# micro.net
KiCad netlist of a schematic drawn in Altium Designer
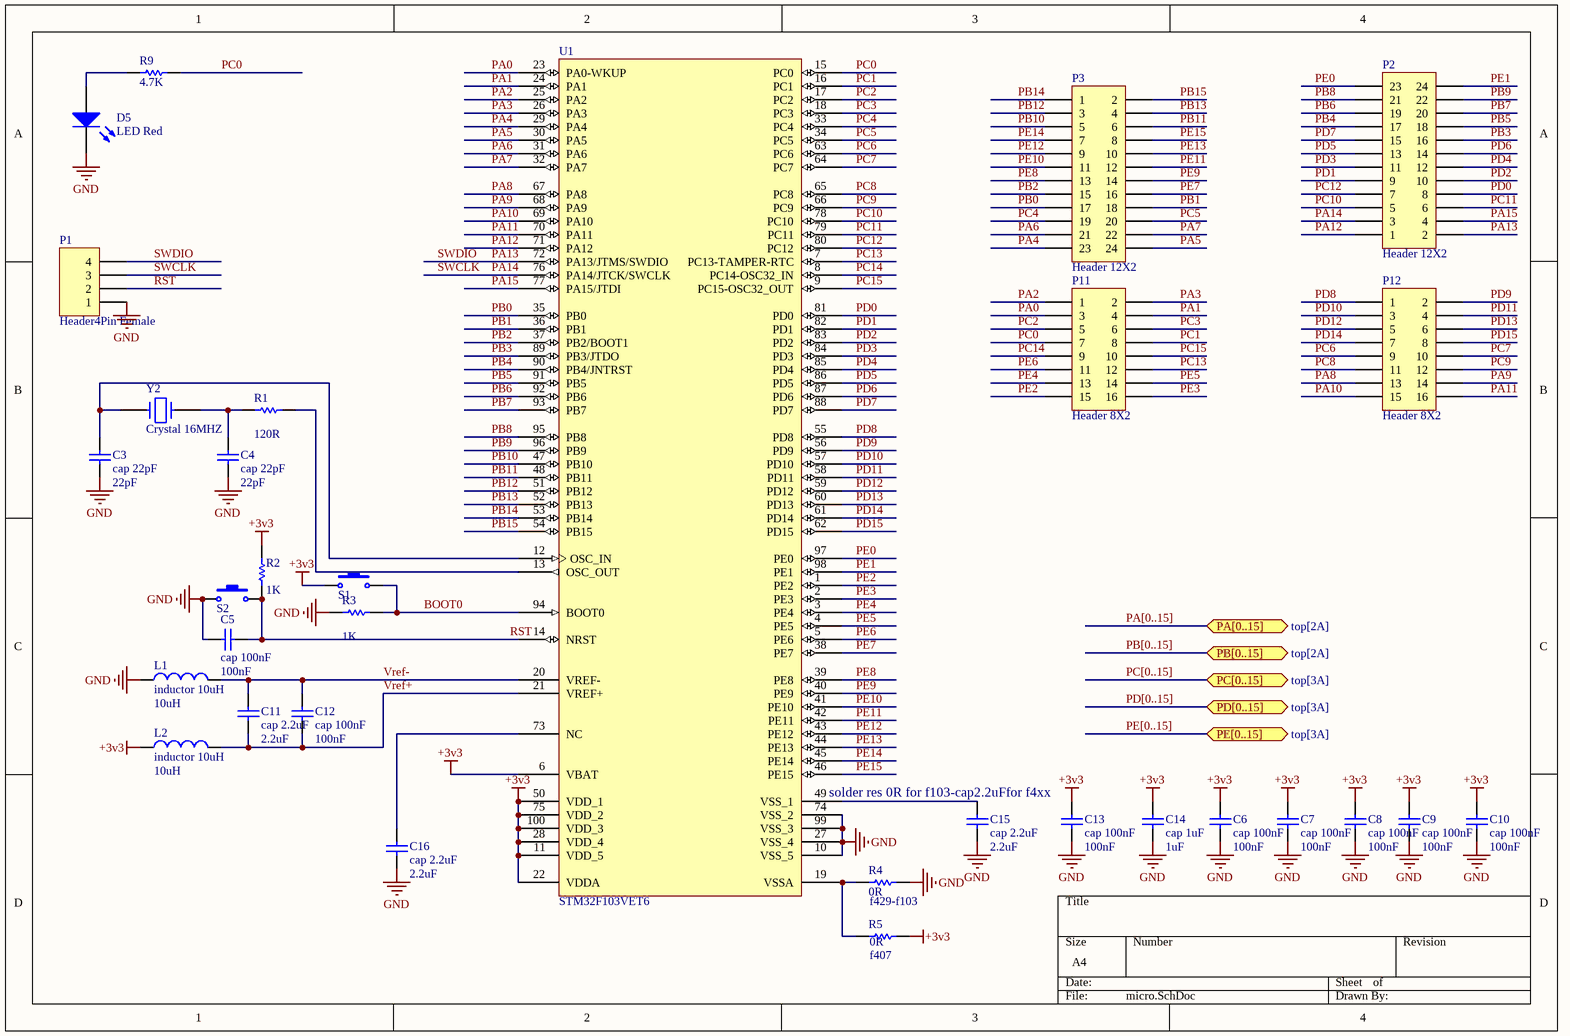
[diagram p0: micro.SchDoc]

(export (version "E")
  (design (tool "Eeschema 10.0.6"))
  (components
    (comp (ref "C3")
      (value "cap 22pF")
      (footprint "Cap 805")
      (description "Capacitor")
      (fields (field (name "ALTIUM_VALUE") "22pF") (field (name "PUBLISHER") "Altium Limited"))
      (libsource (lib "Miscellaneous Devices") (part "Cap"))
    )
    (comp (ref "C4")
      (value "cap 22pF")
      (footprint "Cap 805")
      (description "Capacitor")
      (fields (field (name "ALTIUM_VALUE") "22pF") (field (name "PUBLISHER") "Altium Limited"))
      (libsource (lib "Miscellaneous Devices") (part "Cap"))
    )
    (comp (ref "C5")
      (value "cap 100nF")
      (footprint "Cap 805")
      (description "Capacitor")
      (fields (field (name "ALTIUM_VALUE") "100nF") (field (name "PUBLISHER") "Altium Limited"))
      (libsource (lib "Miscellaneous Devices") (part "Cap"))
    )
    (comp (ref "C6")
      (value "cap 100nF")
      (footprint "Cap 805")
      (description "Capacitor")
      (fields (field (name "ALTIUM_VALUE") "100nF") (field (name "PUBLISHER") "Altium Limited"))
      (libsource (lib "Miscellaneous Devices") (part "Cap"))
    )
    (comp (ref "C7")
      (value "cap 100nF")
      (footprint "Cap 805")
      (description "Capacitor")
      (fields (field (name "ALTIUM_VALUE") "100nF") (field (name "PUBLISHER") "Altium Limited"))
      (libsource (lib "Miscellaneous Devices") (part "Cap"))
    )
    (comp (ref "C8")
      (value "cap 100nF")
      (footprint "Cap 805")
      (description "Capacitor")
      (fields (field (name "ALTIUM_VALUE") "100nF") (field (name "PUBLISHER") "Altium Limited"))
      (libsource (lib "Miscellaneous Devices") (part "Cap"))
    )
    (comp (ref "C9")
      (value "cap 100nF")
      (footprint "Cap 805")
      (description "Capacitor")
      (fields (field (name "ALTIUM_VALUE") "100nF") (field (name "PUBLISHER") "Altium Limited"))
      (libsource (lib "Miscellaneous Devices") (part "Cap"))
    )
    (comp (ref "C10")
      (value "cap 100nF")
      (footprint "Cap 805")
      (description "Capacitor")
      (fields (field (name "ALTIUM_VALUE") "100nF") (field (name "PUBLISHER") "Altium Limited"))
      (libsource (lib "Miscellaneous Devices") (part "Cap"))
    )
    (comp (ref "C11")
      (value "cap 2.2uF")
      (footprint "Cap 805")
      (description "Capacitor")
      (fields (field (name "ALTIUM_VALUE") "2.2uF") (field (name "PUBLISHER") "Altium Limited"))
      (libsource (lib "Miscellaneous Devices") (part "Cap"))
    )
    (comp (ref "C12")
      (value "cap 100nF")
      (footprint "Cap 805")
      (description "Capacitor")
      (fields (field (name "ALTIUM_VALUE") "100nF") (field (name "PUBLISHER") "Altium Limited"))
      (libsource (lib "Miscellaneous Devices") (part "Cap"))
    )
    (comp (ref "C13")
      (value "cap 100nF")
      (footprint "Cap 805")
      (description "Capacitor")
      (fields (field (name "ALTIUM_VALUE") "100nF") (field (name "PUBLISHER") "Altium Limited"))
      (libsource (lib "Miscellaneous Devices") (part "Cap"))
    )
    (comp (ref "C14")
      (value "cap 1uF")
      (footprint "Cap 805")
      (description "Capacitor")
      (fields (field (name "ALTIUM_VALUE") "1uF") (field (name "PUBLISHER") "Altium Limited"))
      (libsource (lib "Miscellaneous Devices") (part "Cap"))
    )
    (comp (ref "C15")
      (value "cap 2.2uF")
      (footprint "Cap 805")
      (description "Capacitor")
      (fields (field (name "ALTIUM_VALUE") "2.2uF") (field (name "PUBLISHER") "Altium Limited"))
      (libsource (lib "Miscellaneous Devices") (part "Cap"))
    )
    (comp (ref "C16")
      (value "cap 2.2uF")
      (footprint "Cap 805")
      (description "Capacitor")
      (fields (field (name "ALTIUM_VALUE") "2.2uF") (field (name "PUBLISHER") "Altium Limited"))
      (libsource (lib "Miscellaneous Devices") (part "Cap"))
    )
    (comp (ref "D5")
      (value "LED Red")
      (footprint "0805-LED")
      (description "LED SMD")
      (fields (field (name "PUBLISHER") "Altium Limited"))
      (libsource (lib "Miscellaneous Devices") (part "LED0"))
    )
    (comp (ref "L1")
      (value "inductor 10uH")
      (footprint "IND1206")
      (description "Inductor")
      (fields (field (name "ALTIUM_VALUE") "10uH") (field (name "PUBLISHER") "Altium Limited"))
      (libsource (lib "Miscellaneous Devices") (part "Inductor"))
    )
    (comp (ref "L2")
      (value "inductor 10uH")
      (footprint "IND1206")
      (description "Inductor")
      (fields (field (name "ALTIUM_VALUE") "10uH") (field (name "PUBLISHER") "Altium Limited"))
      (libsource (lib "Miscellaneous Devices") (part "Inductor"))
    )
    (comp (ref "P1")
      (value "Header4Pin Female")
      (footprint "HDR1X4")
      (description "Header, 4-Pin")
      (fields (field (name "PUBLISHER") "Altium Limited"))
      (libsource (lib "Miscellaneous Connectors") (part "Header 4"))
    )
    (comp (ref "P2")
      (value "Header 12X2")
      (footprint "HDR2X12")
      (description "Header, 12-Pin, Dual row")
      (fields (field (name "PUBLISHER") "Altium Limited"))
      (libsource (lib "") (part "Header 12X2_1"))
    )
    (comp (ref "P3")
      (value "Header 12X2")
      (footprint "HDR2X12")
      (description "Header, 12-Pin, Dual row")
      (fields (field (name "PUBLISHER") "Altium Limited"))
      (libsource (lib "Miscellaneous Connectors") (part "Header 12X2"))
    )
    (comp (ref "P11")
      (value "Header 8X2")
      (footprint "HDR2X8")
      (description "Header, 8-Pin, Dual row")
      (fields (field (name "PUBLISHER") "Altium Limited"))
      (libsource (lib "Miscellaneous Connectors") (part "Header 8X2"))
    )
    (comp (ref "P12")
      (value "Header 8X2")
      (footprint "HDR2X8")
      (description "Header, 8-Pin, Dual row")
      (fields (field (name "PUBLISHER") "Altium Limited"))
      (libsource (lib "Miscellaneous Connectors") (part "Header 8X2"))
    )
    (comp (ref "R1")
      (value "120R")
      (footprint "RES 0805 (2012X06L)")
      (description "Resistor")
      (fields (field (name "Comment") "Res 120R") (field (name "PUBLISHER") "Altium Limited"))
      (libsource (lib "Miscellaneous Devices") (part "Res1"))
    )
    (comp (ref "R2")
      (value "1K")
      (footprint "RES 0805 (2012X06L)")
      (description "Resistor")
      (fields (field (name "Comment") "Res 1K") (field (name "PUBLISHER") "Altium Limited"))
      (libsource (lib "Miscellaneous Devices") (part "Res1"))
    )
    (comp (ref "R3")
      (value "1K")
      (footprint "RES 0805 (2012X06L)")
      (description "Resistor")
      (fields (field (name "Comment") "Res 1K") (field (name "PUBLISHER") "Altium Limited"))
      (libsource (lib "Miscellaneous Devices") (part "Res1"))
    )
    (comp (ref "R4")
      (value "f429-f103")
      (footprint "RES 0805 (2012X06L)")
      (description "Resistor")
      (fields (field (name "ALTIUM_VALUE") "0R") (field (name "PUBLISHER") "Altium Limited"))
      (libsource (lib "Miscellaneous Devices") (part "Res1"))
    )
    (comp (ref "R5")
      (value "f407")
      (footprint "RES 0805 (2012X06L)")
      (description "Resistor")
      (fields (field (name "ALTIUM_VALUE") "0R") (field (name "PUBLISHER") "Altium Limited"))
      (libsource (lib "Miscellaneous Devices") (part "Res1"))
    )
    (comp (ref "R9")
      (value "4.7K")
      (footprint "RES 0805 (2012X06L)")
      (description "Resistor")
      (fields (field (name "Comment") "Res 4.7K") (field (name "PUBLISHER") "Altium Limited"))
      (libsource (lib "Miscellaneous Devices") (part "Res1"))
    )
    (comp (ref "S1")
      (value "Switch PB")
      (footprint "Switch - Push to On")
      (description "Push Button Switch")
      (libsource (lib "Altium (2)") (part "Switch PB"))
    )
    (comp (ref "S2")
      (value "Switch PB")
      (footprint "Switch - Push to On")
      (description "Push Button Switch")
      (libsource (lib "Altium (2)") (part "Switch PB"))
    )
    (comp (ref "U1")
      (value "STM32F103VET6")
      (footprint "LQFP100_N")
      (description "STM32 ARM-based 32-bit MCU with 64 Kbytes Flash, 100-pin LQFP, Industrial Temperature")
      (fields (field (name "PUBLISHER") "Altium Limited"))
      (libsource (lib "ST Microcontroller 32-Bit STM32") (part "STM32F103V8T6"))
    )
    (comp (ref "Y2")
      (value "Crystal 16MHZ")
      (footprint "CRYSTAL Small")
      (description "Crystal")
      (libsource (lib "Altium library (www.AVRelec.com)") (part "CRYSTAL"))
    )
  )
  (nets
    (net (code "1") (name "+3v3") (class "Default")
      (node (ref "C10") (pin "2") (pinfunction "2_2") (pintype "passive"))
      (node (ref "C13") (pin "2") (pinfunction "2_2") (pintype "passive"))
      (node (ref "C14") (pin "2") (pinfunction "2_2") (pintype "passive"))
      (node (ref "C6") (pin "2") (pinfunction "2_2") (pintype "passive"))
      (node (ref "C7") (pin "2") (pinfunction "2_2") (pintype "passive"))
      (node (ref "C8") (pin "2") (pinfunction "2_2") (pintype "passive"))
      (node (ref "C9") (pin "2") (pinfunction "2_2") (pintype "passive"))
      (node (ref "L2") (pin "1") (pinfunction "1_1") (pintype "passive"))
      (node (ref "R2") (pin "1") (pinfunction "1_1") (pintype "passive"))
      (node (ref "R5") (pin "2") (pinfunction "2_2") (pintype "passive"))
      (node (ref "S1") (pin "1") (pinfunction "1_1") (pintype "passive"))
      (node (ref "U1") (pin "100") (pinfunction "VDD_3_100") (pintype "power_in"))
      (node (ref "U1") (pin "11") (pinfunction "VDD_5_11") (pintype "power_in"))
      (node (ref "U1") (pin "22") (pinfunction "VDDA_22") (pintype "power_in"))
      (node (ref "U1") (pin "28") (pinfunction "VDD_4_28") (pintype "power_in"))
      (node (ref "U1") (pin "50") (pinfunction "VDD_1_50") (pintype "power_in"))
      (node (ref "U1") (pin "6") (pinfunction "VBAT_6") (pintype "power_in"))
      (node (ref "U1") (pin "75") (pinfunction "VDD_2_75") (pintype "power_in"))
    )
    (net (code "2") (name "/BOOT0") (class "Default")
      (node (ref "R3") (pin "2") (pinfunction "2_2") (pintype "passive"))
      (node (ref "S1") (pin "2") (pinfunction "2_2") (pintype "passive"))
      (node (ref "U1") (pin "94") (pinfunction "BOOT0_94") (pintype "input"))
    )
    (net (code "3") (name "/PA0") (class "Default")
      (node (ref "P11") (pin "3") (pinfunction "3_3") (pintype "passive"))
      (node (ref "U1") (pin "23") (pinfunction "PA0-WKUP_23") (pintype "bidirectional"))
    )
    (net (code "4") (name "/PA1") (class "Default")
      (node (ref "P11") (pin "4") (pinfunction "4_4") (pintype "passive"))
      (node (ref "U1") (pin "24") (pinfunction "PA1_24") (pintype "bidirectional"))
    )
    (net (code "5") (name "/PA2") (class "Default")
      (node (ref "P11") (pin "1") (pinfunction "1_1") (pintype "passive"))
      (node (ref "U1") (pin "25") (pinfunction "PA2_25") (pintype "bidirectional"))
    )
    (net (code "6") (name "/PA3") (class "Default")
      (node (ref "P11") (pin "2") (pinfunction "2_2") (pintype "passive"))
      (node (ref "U1") (pin "26") (pinfunction "PA3_26") (pintype "bidirectional"))
    )
    (net (code "7") (name "/PA4") (class "Default")
      (node (ref "P3") (pin "23") (pinfunction "23_23") (pintype "passive"))
      (node (ref "U1") (pin "29") (pinfunction "PA4_29") (pintype "bidirectional"))
    )
    (net (code "8") (name "/PA5") (class "Default")
      (node (ref "P3") (pin "24") (pinfunction "24_24") (pintype "passive"))
      (node (ref "U1") (pin "30") (pinfunction "PA5_30") (pintype "bidirectional"))
    )
    (net (code "9") (name "/PA6") (class "Default")
      (node (ref "P3") (pin "21") (pinfunction "21_21") (pintype "passive"))
      (node (ref "U1") (pin "31") (pinfunction "PA6_31") (pintype "bidirectional"))
    )
    (net (code "10") (name "/PA7") (class "Default")
      (node (ref "P3") (pin "22") (pinfunction "22_22") (pintype "passive"))
      (node (ref "U1") (pin "32") (pinfunction "PA7_32") (pintype "bidirectional"))
    )
    (net (code "11") (name "/PA8") (class "Default")
      (node (ref "P12") (pin "13") (pinfunction "13_13") (pintype "passive"))
      (node (ref "U1") (pin "67") (pinfunction "PA8_67") (pintype "bidirectional"))
    )
    (net (code "12") (name "/PA9") (class "Default")
      (node (ref "P12") (pin "14") (pinfunction "14_14") (pintype "passive"))
      (node (ref "U1") (pin "68") (pinfunction "PA9_68") (pintype "bidirectional"))
    )
    (net (code "13") (name "/PA10") (class "Default")
      (node (ref "P12") (pin "15") (pinfunction "15_15") (pintype "passive"))
      (node (ref "U1") (pin "69") (pinfunction "PA10_69") (pintype "bidirectional"))
    )
    (net (code "14") (name "/PA11") (class "Default")
      (node (ref "P12") (pin "16") (pinfunction "16_16") (pintype "passive"))
      (node (ref "U1") (pin "70") (pinfunction "PA11_70") (pintype "bidirectional"))
    )
    (net (code "15") (name "/PA12") (class "Default")
      (node (ref "P2") (pin "1") (pinfunction "1_1") (pintype "passive"))
      (node (ref "U1") (pin "71") (pinfunction "PA12_71") (pintype "bidirectional"))
    )
    (net (code "16") (name "/PA13") (class "Default")
      (node (ref "P1") (pin "4") (pinfunction "4_4") (pintype "passive"))
      (node (ref "P2") (pin "2") (pinfunction "2_2") (pintype "passive"))
      (node (ref "U1") (pin "72") (pinfunction "PA13/JTMS/SWDIO_72") (pintype "bidirectional"))
    )
    (net (code "17") (name "/PA14") (class "Default")
      (node (ref "P1") (pin "3") (pinfunction "3_3") (pintype "passive"))
      (node (ref "P2") (pin "3") (pinfunction "3_3") (pintype "passive"))
      (node (ref "U1") (pin "76") (pinfunction "PA14/JTCK/SWCLK_76") (pintype "bidirectional"))
    )
    (net (code "18") (name "/PA15") (class "Default")
      (node (ref "P2") (pin "4") (pinfunction "4_4") (pintype "passive"))
      (node (ref "U1") (pin "77") (pinfunction "PA15/JTDI_77") (pintype "bidirectional"))
    )
    (net (code "20") (name "/PB0") (class "Default")
      (node (ref "P3") (pin "17") (pinfunction "17_17") (pintype "passive"))
      (node (ref "U1") (pin "35") (pinfunction "PB0_35") (pintype "bidirectional"))
    )
    (net (code "21") (name "/PB1") (class "Default")
      (node (ref "P3") (pin "18") (pinfunction "18_18") (pintype "passive"))
      (node (ref "U1") (pin "36") (pinfunction "PB1_36") (pintype "bidirectional"))
    )
    (net (code "22") (name "/PB2") (class "Default")
      (node (ref "P3") (pin "15") (pinfunction "15_15") (pintype "passive"))
      (node (ref "U1") (pin "37") (pinfunction "PB2/BOOT1_37") (pintype "bidirectional"))
    )
    (net (code "23") (name "/PB3") (class "Default")
      (node (ref "P2") (pin "16") (pinfunction "16_16") (pintype "passive"))
      (node (ref "U1") (pin "89") (pinfunction "PB3/JTDO_89") (pintype "bidirectional"))
    )
    (net (code "24") (name "/PB4") (class "Default")
      (node (ref "P2") (pin "17") (pinfunction "17_17") (pintype "passive"))
      (node (ref "U1") (pin "90") (pinfunction "PB4/JNTRST_90") (pintype "bidirectional"))
    )
    (net (code "25") (name "/PB5") (class "Default")
      (node (ref "P2") (pin "18") (pinfunction "18_18") (pintype "passive"))
      (node (ref "U1") (pin "91") (pinfunction "PB5_91") (pintype "bidirectional"))
    )
    (net (code "26") (name "/PB6") (class "Default")
      (node (ref "P2") (pin "19") (pinfunction "19_19") (pintype "passive"))
      (node (ref "U1") (pin "92") (pinfunction "PB6_92") (pintype "bidirectional"))
    )
    (net (code "27") (name "/PB7") (class "Default")
      (node (ref "P2") (pin "20") (pinfunction "20_20") (pintype "passive"))
      (node (ref "U1") (pin "93") (pinfunction "PB7_93") (pintype "bidirectional"))
    )
    (net (code "28") (name "/PB8") (class "Default")
      (node (ref "P2") (pin "21") (pinfunction "21_21") (pintype "passive"))
      (node (ref "U1") (pin "95") (pinfunction "PB8_95") (pintype "bidirectional"))
    )
    (net (code "29") (name "/PB9") (class "Default")
      (node (ref "P2") (pin "22") (pinfunction "22_22") (pintype "passive"))
      (node (ref "U1") (pin "96") (pinfunction "PB9_96") (pintype "bidirectional"))
    )
    (net (code "30") (name "/PB10") (class "Default")
      (node (ref "P3") (pin "5") (pinfunction "5_5") (pintype "passive"))
      (node (ref "U1") (pin "47") (pinfunction "PB10_47") (pintype "bidirectional"))
    )
    (net (code "31") (name "/PB11") (class "Default")
      (node (ref "P3") (pin "6") (pinfunction "6_6") (pintype "passive"))
      (node (ref "U1") (pin "48") (pinfunction "PB11_48") (pintype "bidirectional"))
    )
    (net (code "32") (name "/PB12") (class "Default")
      (node (ref "P3") (pin "3") (pinfunction "3_3") (pintype "passive"))
      (node (ref "U1") (pin "51") (pinfunction "PB12_51") (pintype "bidirectional"))
    )
    (net (code "33") (name "/PB13") (class "Default")
      (node (ref "P3") (pin "4") (pinfunction "4_4") (pintype "passive"))
      (node (ref "U1") (pin "52") (pinfunction "PB13_52") (pintype "bidirectional"))
    )
    (net (code "34") (name "/PB14") (class "Default")
      (node (ref "P3") (pin "1") (pinfunction "1_1") (pintype "passive"))
      (node (ref "U1") (pin "53") (pinfunction "PB14_53") (pintype "bidirectional"))
    )
    (net (code "35") (name "/PB15") (class "Default")
      (node (ref "P3") (pin "2") (pinfunction "2_2") (pintype "passive"))
      (node (ref "U1") (pin "54") (pinfunction "PB15_54") (pintype "bidirectional"))
    )
    (net (code "37") (name "/PC0") (class "Default")
      (node (ref "P11") (pin "7") (pinfunction "7_7") (pintype "passive"))
      (node (ref "R9") (pin "1") (pinfunction "1_1") (pintype "passive"))
      (node (ref "U1") (pin "15") (pinfunction "PC0_15") (pintype "bidirectional"))
    )
    (net (code "38") (name "/PC1") (class "Default")
      (node (ref "P11") (pin "8") (pinfunction "8_8") (pintype "passive"))
      (node (ref "U1") (pin "16") (pinfunction "PC1_16") (pintype "bidirectional"))
    )
    (net (code "39") (name "/PC2") (class "Default")
      (node (ref "P11") (pin "5") (pinfunction "5_5") (pintype "passive"))
      (node (ref "U1") (pin "17") (pinfunction "PC2_17") (pintype "bidirectional"))
    )
    (net (code "40") (name "/PC3") (class "Default")
      (node (ref "P11") (pin "6") (pinfunction "6_6") (pintype "passive"))
      (node (ref "U1") (pin "18") (pinfunction "PC3_18") (pintype "bidirectional"))
    )
    (net (code "41") (name "/PC4") (class "Default")
      (node (ref "P3") (pin "19") (pinfunction "19_19") (pintype "passive"))
      (node (ref "U1") (pin "33") (pinfunction "PC4_33") (pintype "bidirectional"))
    )
    (net (code "42") (name "/PC5") (class "Default")
      (node (ref "P3") (pin "20") (pinfunction "20_20") (pintype "passive"))
      (node (ref "U1") (pin "34") (pinfunction "PC5_34") (pintype "bidirectional"))
    )
    (net (code "43") (name "/PC6") (class "Default")
      (node (ref "P12") (pin "9") (pinfunction "9_9") (pintype "passive"))
      (node (ref "U1") (pin "63") (pinfunction "PC6_63") (pintype "bidirectional"))
    )
    (net (code "44") (name "/PC7") (class "Default")
      (node (ref "P12") (pin "10") (pinfunction "10_10") (pintype "passive"))
      (node (ref "U1") (pin "64") (pinfunction "PC7_64") (pintype "bidirectional"))
    )
    (net (code "45") (name "/PC8") (class "Default")
      (node (ref "P12") (pin "11") (pinfunction "11_11") (pintype "passive"))
      (node (ref "U1") (pin "65") (pinfunction "PC8_65") (pintype "bidirectional"))
    )
    (net (code "46") (name "/PC9") (class "Default")
      (node (ref "P12") (pin "12") (pinfunction "12_12") (pintype "passive"))
      (node (ref "U1") (pin "66") (pinfunction "PC9_66") (pintype "bidirectional"))
    )
    (net (code "47") (name "/PC10") (class "Default")
      (node (ref "P2") (pin "5") (pinfunction "5_5") (pintype "passive"))
      (node (ref "U1") (pin "78") (pinfunction "PC10_78") (pintype "bidirectional"))
    )
    (net (code "48") (name "/PC11") (class "Default")
      (node (ref "P2") (pin "6") (pinfunction "6_6") (pintype "passive"))
      (node (ref "U1") (pin "79") (pinfunction "PC11_79") (pintype "bidirectional"))
    )
    (net (code "49") (name "/PC12") (class "Default")
      (node (ref "P2") (pin "7") (pinfunction "7_7") (pintype "passive"))
      (node (ref "U1") (pin "80") (pinfunction "PC12_80") (pintype "bidirectional"))
    )
    (net (code "50") (name "/PC13") (class "Default")
      (node (ref "P11") (pin "12") (pinfunction "12_12") (pintype "passive"))
      (node (ref "U1") (pin "7") (pinfunction "PC13-TAMPER-RTC_7") (pintype "bidirectional"))
    )
    (net (code "51") (name "/PC14") (class "Default")
      (node (ref "P11") (pin "9") (pinfunction "9_9") (pintype "passive"))
      (node (ref "U1") (pin "8") (pinfunction "PC14-OSC32_IN_8") (pintype "bidirectional"))
    )
    (net (code "52") (name "/PC15") (class "Default")
      (node (ref "P11") (pin "10") (pinfunction "10_10") (pintype "passive"))
      (node (ref "U1") (pin "9") (pinfunction "PC15-OSC32_OUT_9") (pintype "bidirectional"))
    )
    (net (code "54") (name "/PD0") (class "Default")
      (node (ref "P2") (pin "8") (pinfunction "8_8") (pintype "passive"))
      (node (ref "U1") (pin "81") (pinfunction "PD0_81") (pintype "bidirectional"))
    )
    (net (code "55") (name "/PD1") (class "Default")
      (node (ref "P2") (pin "9") (pinfunction "9_9") (pintype "passive"))
      (node (ref "U1") (pin "82") (pinfunction "PD1_82") (pintype "bidirectional"))
    )
    (net (code "56") (name "/PD2") (class "Default")
      (node (ref "P2") (pin "10") (pinfunction "10_10") (pintype "passive"))
      (node (ref "U1") (pin "83") (pinfunction "PD2_83") (pintype "bidirectional"))
    )
    (net (code "57") (name "/PD3") (class "Default")
      (node (ref "P2") (pin "11") (pinfunction "11_11") (pintype "passive"))
      (node (ref "U1") (pin "84") (pinfunction "PD3_84") (pintype "bidirectional"))
    )
    (net (code "58") (name "/PD4") (class "Default")
      (node (ref "P2") (pin "12") (pinfunction "12_12") (pintype "passive"))
      (node (ref "U1") (pin "85") (pinfunction "PD4_85") (pintype "bidirectional"))
    )
    (net (code "59") (name "/PD5") (class "Default")
      (node (ref "P2") (pin "13") (pinfunction "13_13") (pintype "passive"))
      (node (ref "U1") (pin "86") (pinfunction "PD5_86") (pintype "bidirectional"))
    )
    (net (code "60") (name "/PD6") (class "Default")
      (node (ref "P2") (pin "14") (pinfunction "14_14") (pintype "passive"))
      (node (ref "U1") (pin "87") (pinfunction "PD6_87") (pintype "bidirectional"))
    )
    (net (code "61") (name "/PD7") (class "Default")
      (node (ref "P2") (pin "15") (pinfunction "15_15") (pintype "passive"))
      (node (ref "U1") (pin "88") (pinfunction "PD7_88") (pintype "bidirectional"))
    )
    (net (code "62") (name "/PD8") (class "Default")
      (node (ref "P12") (pin "1") (pinfunction "1_1") (pintype "passive"))
      (node (ref "U1") (pin "55") (pinfunction "PD8_55") (pintype "bidirectional"))
    )
    (net (code "63") (name "/PD9") (class "Default")
      (node (ref "P12") (pin "2") (pinfunction "2_2") (pintype "passive"))
      (node (ref "U1") (pin "56") (pinfunction "PD9_56") (pintype "bidirectional"))
    )
    (net (code "64") (name "/PD10") (class "Default")
      (node (ref "P12") (pin "3") (pinfunction "3_3") (pintype "passive"))
      (node (ref "U1") (pin "57") (pinfunction "PD10_57") (pintype "bidirectional"))
    )
    (net (code "65") (name "/PD11") (class "Default")
      (node (ref "P12") (pin "4") (pinfunction "4_4") (pintype "passive"))
      (node (ref "U1") (pin "58") (pinfunction "PD11_58") (pintype "bidirectional"))
    )
    (net (code "66") (name "/PD12") (class "Default")
      (node (ref "P12") (pin "5") (pinfunction "5_5") (pintype "passive"))
      (node (ref "U1") (pin "59") (pinfunction "PD12_59") (pintype "bidirectional"))
    )
    (net (code "67") (name "/PD13") (class "Default")
      (node (ref "P12") (pin "6") (pinfunction "6_6") (pintype "passive"))
      (node (ref "U1") (pin "60") (pinfunction "PD13_60") (pintype "bidirectional"))
    )
    (net (code "68") (name "/PD14") (class "Default")
      (node (ref "P12") (pin "7") (pinfunction "7_7") (pintype "passive"))
      (node (ref "U1") (pin "61") (pinfunction "PD14_61") (pintype "bidirectional"))
    )
    (net (code "69") (name "/PD15") (class "Default")
      (node (ref "P12") (pin "8") (pinfunction "8_8") (pintype "passive"))
      (node (ref "U1") (pin "62") (pinfunction "PD15_62") (pintype "bidirectional"))
    )
    (net (code "71") (name "/PE0") (class "Default")
      (node (ref "P2") (pin "23") (pinfunction "23_23") (pintype "passive"))
      (node (ref "U1") (pin "97") (pinfunction "PE0_97") (pintype "bidirectional"))
    )
    (net (code "72") (name "/PE1") (class "Default")
      (node (ref "P2") (pin "24") (pinfunction "24_24") (pintype "passive"))
      (node (ref "U1") (pin "98") (pinfunction "PE1_98") (pintype "bidirectional"))
    )
    (net (code "73") (name "/PE2") (class "Default")
      (node (ref "P11") (pin "15") (pinfunction "15_15") (pintype "passive"))
      (node (ref "U1") (pin "1") (pinfunction "PE2_1") (pintype "bidirectional"))
    )
    (net (code "74") (name "/PE3") (class "Default")
      (node (ref "P11") (pin "16") (pinfunction "16_16") (pintype "passive"))
      (node (ref "U1") (pin "2") (pinfunction "PE3_2") (pintype "bidirectional"))
    )
    (net (code "75") (name "/PE4") (class "Default")
      (node (ref "P11") (pin "13") (pinfunction "13_13") (pintype "passive"))
      (node (ref "U1") (pin "3") (pinfunction "PE4_3") (pintype "bidirectional"))
    )
    (net (code "76") (name "/PE5") (class "Default")
      (node (ref "P11") (pin "14") (pinfunction "14_14") (pintype "passive"))
      (node (ref "U1") (pin "4") (pinfunction "PE5_4") (pintype "bidirectional"))
    )
    (net (code "77") (name "/PE6") (class "Default")
      (node (ref "P11") (pin "11") (pinfunction "11_11") (pintype "passive"))
      (node (ref "U1") (pin "5") (pinfunction "PE6_5") (pintype "bidirectional"))
    )
    (net (code "78") (name "/PE7") (class "Default")
      (node (ref "P3") (pin "16") (pinfunction "16_16") (pintype "passive"))
      (node (ref "U1") (pin "38") (pinfunction "PE7_38") (pintype "bidirectional"))
    )
    (net (code "79") (name "/PE8") (class "Default")
      (node (ref "P3") (pin "13") (pinfunction "13_13") (pintype "passive"))
      (node (ref "U1") (pin "39") (pinfunction "PE8_39") (pintype "bidirectional"))
    )
    (net (code "80") (name "/PE9") (class "Default")
      (node (ref "P3") (pin "14") (pinfunction "14_14") (pintype "passive"))
      (node (ref "U1") (pin "40") (pinfunction "PE9_40") (pintype "bidirectional"))
    )
    (net (code "81") (name "/PE10") (class "Default")
      (node (ref "P3") (pin "11") (pinfunction "11_11") (pintype "passive"))
      (node (ref "U1") (pin "41") (pinfunction "PE10_41") (pintype "bidirectional"))
    )
    (net (code "82") (name "/PE11") (class "Default")
      (node (ref "P3") (pin "12") (pinfunction "12_12") (pintype "passive"))
      (node (ref "U1") (pin "42") (pinfunction "PE11_42") (pintype "bidirectional"))
    )
    (net (code "83") (name "/PE12") (class "Default")
      (node (ref "P3") (pin "9") (pinfunction "9_9") (pintype "passive"))
      (node (ref "U1") (pin "43") (pinfunction "PE12_43") (pintype "bidirectional"))
    )
    (net (code "84") (name "/PE13") (class "Default")
      (node (ref "P3") (pin "10") (pinfunction "10_10") (pintype "passive"))
      (node (ref "U1") (pin "44") (pinfunction "PE13_44") (pintype "bidirectional"))
    )
    (net (code "85") (name "/PE14") (class "Default")
      (node (ref "P3") (pin "7") (pinfunction "7_7") (pintype "passive"))
      (node (ref "U1") (pin "45") (pinfunction "PE14_45") (pintype "bidirectional"))
    )
    (net (code "86") (name "/PE15") (class "Default")
      (node (ref "P3") (pin "8") (pinfunction "8_8") (pintype "passive"))
      (node (ref "U1") (pin "46") (pinfunction "PE15_46") (pintype "bidirectional"))
    )
    (net (code "88") (name "/RST") (class "Default")
      (node (ref "C5") (pin "1") (pinfunction "1_1") (pintype "passive"))
      (node (ref "P1") (pin "2") (pinfunction "2_2") (pintype "passive"))
      (node (ref "R2") (pin "2") (pinfunction "2_2") (pintype "passive"))
      (node (ref "S2") (pin "2") (pinfunction "2_2") (pintype "passive"))
      (node (ref "U1") (pin "14") (pinfunction "NRST_14") (pintype "bidirectional"))
    )
    (net (code "89") (name "/Vref+") (class "Default")
      (node (ref "C11") (pin "1") (pinfunction "1_1") (pintype "passive"))
      (node (ref "C12") (pin "1") (pinfunction "1_1") (pintype "passive"))
      (node (ref "L2") (pin "2") (pinfunction "2_2") (pintype "passive"))
      (node (ref "U1") (pin "21") (pinfunction "VREF+_21") (pintype "power_in"))
    )
    (net (code "90") (name "/Vref-") (class "Default")
      (node (ref "C11") (pin "2") (pinfunction "2_2") (pintype "passive"))
      (node (ref "C12") (pin "2") (pinfunction "2_2") (pintype "passive"))
      (node (ref "L1") (pin "2") (pinfunction "2_2") (pintype "passive"))
      (node (ref "U1") (pin "20") (pinfunction "VREF-_20") (pintype "power_in"))
    )
    (net (code "91") (name "GND") (class "Default")
      (node (ref "C10") (pin "1") (pinfunction "1_1") (pintype "passive"))
      (node (ref "C13") (pin "1") (pinfunction "1_1") (pintype "passive"))
      (node (ref "C14") (pin "1") (pinfunction "1_1") (pintype "passive"))
      (node (ref "C15") (pin "1") (pinfunction "1_1") (pintype "passive"))
      (node (ref "C16") (pin "1") (pinfunction "1_1") (pintype "passive"))
      (node (ref "C3") (pin "2") (pinfunction "2_2") (pintype "passive"))
      (node (ref "C4") (pin "1") (pinfunction "1_1") (pintype "passive"))
      (node (ref "C5") (pin "2") (pinfunction "2_2") (pintype "passive"))
      (node (ref "C6") (pin "1") (pinfunction "1_1") (pintype "passive"))
      (node (ref "C7") (pin "1") (pinfunction "1_1") (pintype "passive"))
      (node (ref "C8") (pin "1") (pinfunction "1_1") (pintype "passive"))
      (node (ref "C9") (pin "1") (pinfunction "1_1") (pintype "passive"))
      (node (ref "D5") (pin "2") (pinfunction "K_2") (pintype "passive"))
      (node (ref "L1") (pin "1") (pinfunction "1_1") (pintype "passive"))
      (node (ref "P1") (pin "1") (pinfunction "1_1") (pintype "passive"))
      (node (ref "R3") (pin "1") (pinfunction "1_1") (pintype "passive"))
      (node (ref "R4") (pin "1") (pinfunction "1_1") (pintype "passive"))
      (node (ref "S2") (pin "1") (pinfunction "1_1") (pintype "passive"))
      (node (ref "U1") (pin "10") (pinfunction "VSS_5_10") (pintype "power_in"))
      (node (ref "U1") (pin "27") (pinfunction "VSS_4_27") (pintype "power_in"))
      (node (ref "U1") (pin "74") (pinfunction "VSS_2_74") (pintype "power_in"))
      (node (ref "U1") (pin "99") (pinfunction "VSS_3_99") (pintype "power_in"))
    )
    (net (code "92") (name "Net-(C4-Pad2)") (class "Default")
      (node (ref "C4") (pin "2") (pinfunction "2_2") (pintype "passive"))
      (node (ref "R1") (pin "2") (pinfunction "2_2") (pintype "passive"))
      (node (ref "Y2") (pin "2") (pinfunction "2_2") (pintype "passive"))
    )
    (net (code "93") (name "Net-(D5-A)") (class "Default")
      (node (ref "D5") (pin "1") (pinfunction "A_1") (pintype "passive"))
      (node (ref "R9") (pin "2") (pinfunction "2_2") (pintype "passive"))
    )
    (net (code "94") (name "Net-(U1-NC)") (class "Default")
      (node (ref "C16") (pin "2") (pinfunction "2_2") (pintype "passive"))
      (node (ref "U1") (pin "73") (pinfunction "NC_73") (pintype "passive"))
    )
    (net (code "95") (name "Net-(U1-OSC_IN)") (class "Default")
      (node (ref "C3") (pin "1") (pinfunction "1_1") (pintype "passive"))
      (node (ref "U1") (pin "12") (pinfunction "OSC_IN_12") (pintype "input"))
      (node (ref "Y2") (pin "1") (pinfunction "1_1") (pintype "passive"))
    )
    (net (code "96") (name "Net-(U1-OSC_OUT)") (class "Default")
      (node (ref "R1") (pin "1") (pinfunction "1_1") (pintype "passive"))
      (node (ref "U1") (pin "13") (pinfunction "OSC_OUT_13") (pintype "output"))
    )
    (net (code "97") (name "Net-(U1-VSSA)") (class "Default")
      (node (ref "R4") (pin "2") (pinfunction "2_2") (pintype "passive"))
      (node (ref "R5") (pin "1") (pinfunction "1_1") (pintype "passive"))
      (node (ref "U1") (pin "19") (pinfunction "VSSA_19") (pintype "power_in"))
    )
    (net (code "98") (name "Net-(U1-VSS_1)") (class "Default")
      (node (ref "C15") (pin "2") (pinfunction "2_2") (pintype "passive"))
      (node (ref "U1") (pin "49") (pinfunction "VSS_1_49") (pintype "power_in"))
    )
  )
)
